# Activation.net
KiCad netlist of a schematic drawn in EAGLE
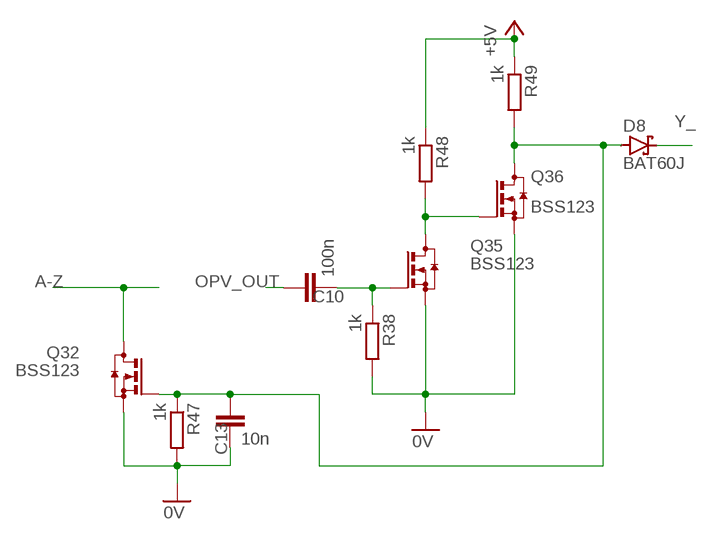
[diagram p0: schematic, sheet 1]

(export (version "E")
  (design (tool "Eeschema 10.0.6"))
  (components
    (comp (ref "C10")
      (value "100n")
      (footprint "eagle-import:C0805")
      (libsource (lib "eagle-import") (part "C-EUC0805"))
    )
    (comp (ref "C13")
      (value "10n")
      (footprint "eagle-import:C0805")
      (libsource (lib "eagle-import") (part "C-EUC0805"))
    )
    (comp (ref "D8")
      (value "BAT60J")
      (footprint "eagle-import:SOD323_ST")
      (libsource (lib "eagle-import") (part "BAT60J"))
    )
    (comp (ref "Q32")
      (value "BSS123")
      (footprint "eagle-import:SOT23")
      (libsource (lib "eagle-import") (part "BSS123"))
    )
    (comp (ref "Q35")
      (value "BSS123")
      (footprint "eagle-import:SOT23")
      (libsource (lib "eagle-import") (part "BSS123"))
    )
    (comp (ref "Q36")
      (value "BSS123")
      (footprint "eagle-import:SOT23")
      (libsource (lib "eagle-import") (part "BSS123"))
    )
    (comp (ref "R38")
      (value "1k")
      (footprint "eagle-import:M0805")
      (libsource (lib "eagle-import") (part "R-EU_M0805"))
    )
    (comp (ref "R47")
      (value "1k")
      (footprint "eagle-import:M0805")
      (libsource (lib "eagle-import") (part "R-EU_M0805"))
    )
    (comp (ref "R48")
      (value "1k")
      (footprint "eagle-import:M0805")
      (libsource (lib "eagle-import") (part "R-EU_M0805"))
    )
    (comp (ref "R49")
      (value "1k")
      (footprint "eagle-import:M0805")
      (libsource (lib "eagle-import") (part "R-EU_M0805"))
    )
  )
  (nets
    (net (code "1") (name "+5V") (class "Default")
      (node (ref "R48") (pin "1") (pinfunction "1_1") (pintype "passive"))
      (node (ref "R49") (pin "1") (pinfunction "1_1") (pintype "passive"))
    )
    (net (code "2") (name "/A-Z") (class "Default")
      (node (ref "Q32") (pin "3") (pinfunction "D_3") (pintype "passive"))
    )
    (net (code "3") (name "/OPV_OUT") (class "Default")
      (node (ref "C10") (pin "1") (pinfunction "1_1") (pintype "passive"))
    )
    (net (code "4") (name "/Y_") (class "Default")
      (node (ref "D8") (pin "C") (pinfunction "C_C") (pintype "passive"))
    )
    (net (code "5") (name "0V") (class "Default")
      (node (ref "C13") (pin "2") (pinfunction "2_2") (pintype "passive"))
      (node (ref "Q32") (pin "2") (pinfunction "S_2") (pintype "passive"))
      (node (ref "Q35") (pin "2") (pinfunction "S_2") (pintype "passive"))
      (node (ref "Q36") (pin "2") (pinfunction "S_2") (pintype "passive"))
      (node (ref "R38") (pin "2") (pinfunction "2_2") (pintype "passive"))
      (node (ref "R47") (pin "2") (pinfunction "2_2") (pintype "passive"))
    )
    (net (code "6") (name "Net-(Q32-G)") (class "Default")
      (node (ref "C13") (pin "1") (pinfunction "1_1") (pintype "passive"))
      (node (ref "D8") (pin "A") (pinfunction "A_A") (pintype "passive"))
      (node (ref "Q32") (pin "1") (pinfunction "G_1") (pintype "passive"))
      (node (ref "Q36") (pin "3") (pinfunction "D_3") (pintype "passive"))
      (node (ref "R47") (pin "1") (pinfunction "1_1") (pintype "passive"))
      (node (ref "R49") (pin "2") (pinfunction "2_2") (pintype "passive"))
    )
    (net (code "7") (name "Net-(Q35-D)") (class "Default")
      (node (ref "Q35") (pin "3") (pinfunction "D_3") (pintype "passive"))
      (node (ref "Q36") (pin "1") (pinfunction "G_1") (pintype "passive"))
      (node (ref "R48") (pin "2") (pinfunction "2_2") (pintype "passive"))
    )
    (net (code "8") (name "Net-(Q35-G)") (class "Default")
      (node (ref "C10") (pin "2") (pinfunction "2_2") (pintype "passive"))
      (node (ref "Q35") (pin "1") (pinfunction "G_1") (pintype "passive"))
      (node (ref "R38") (pin "1") (pinfunction "1_1") (pintype "passive"))
    )
  )
)
